# wemos_d1_mini_pro.net
KiCad netlist of a schematic drawn in EAGLE
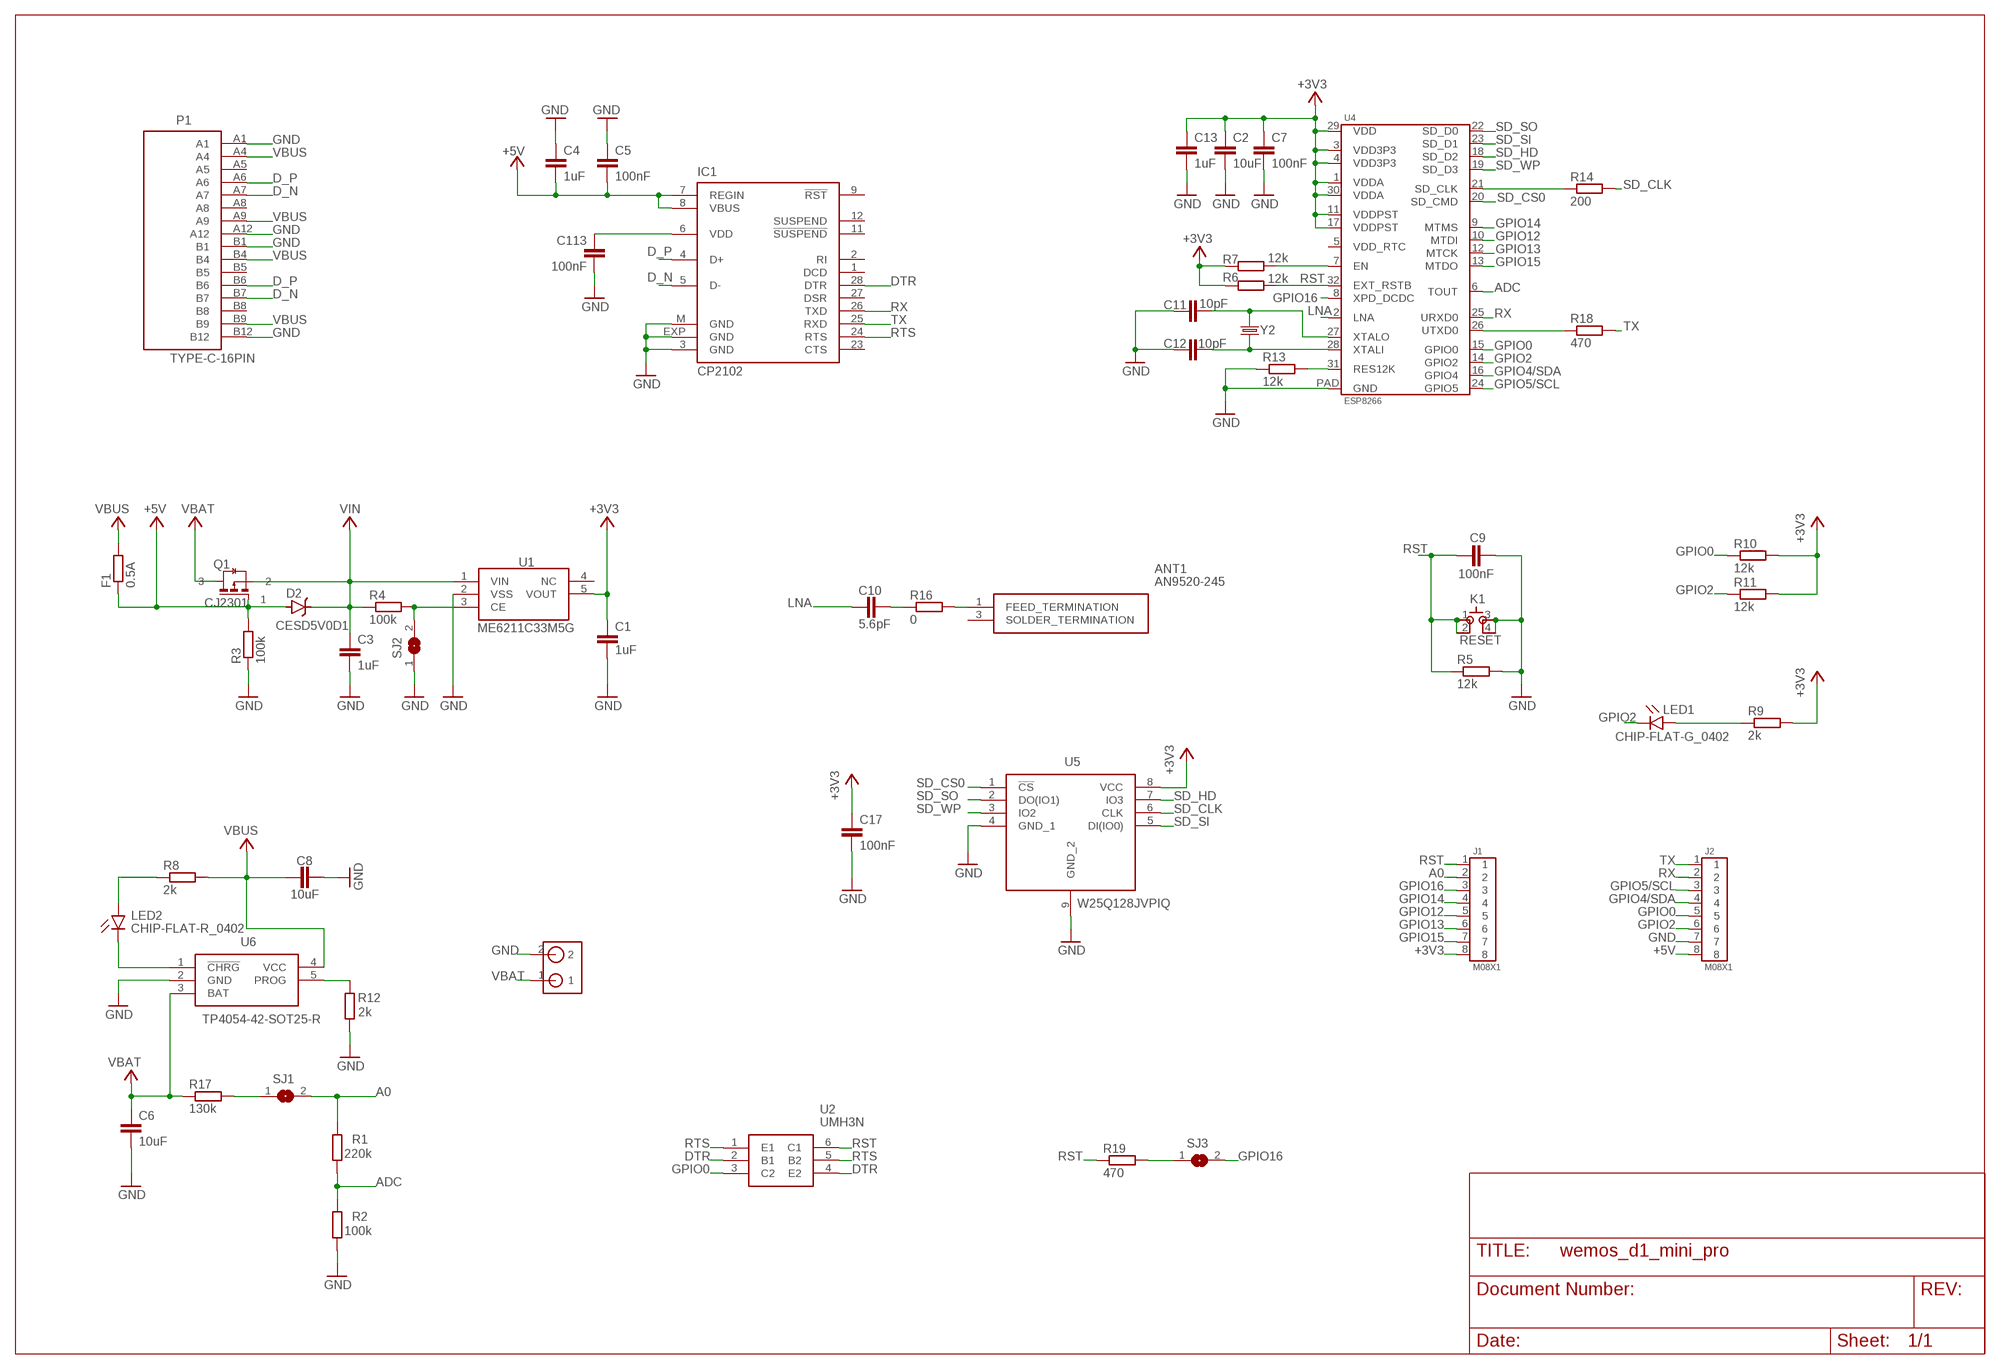
[diagram p0: schematic, sheet 1]

(export (version "E")
  (design (tool "Eeschema 10.0.6"))
  (components
    (comp (ref "ANT1")
      (value "AN9520-245")
      (footprint "eagle-import:AN9520245")
      (libsource (lib "eagle-import") (part "AN9520-245"))
    )
    (comp (ref "C1")
      (value "1uF")
      (footprint "eagle-import:C0402")
      (libsource (lib "eagle-import") (part "C-EUC0402"))
    )
    (comp (ref "C2")
      (value "10uF")
      (footprint "eagle-import:C0402")
      (libsource (lib "eagle-import") (part "C-EUC0402"))
    )
    (comp (ref "C3")
      (value "1uF")
      (footprint "eagle-import:C0402")
      (libsource (lib "eagle-import") (part "C-EUC0402"))
    )
    (comp (ref "C4")
      (value "1uF")
      (footprint "eagle-import:C0402")
      (libsource (lib "eagle-import") (part "C-EUC0402"))
    )
    (comp (ref "C5")
      (value "100nF")
      (footprint "eagle-import:C0402")
      (libsource (lib "eagle-import") (part "C-EUC0402"))
    )
    (comp (ref "C6")
      (value "10uF")
      (footprint "eagle-import:C0402")
      (libsource (lib "eagle-import") (part "C-EUC0402"))
    )
    (comp (ref "C7")
      (value "100nF")
      (footprint "eagle-import:C0402")
      (libsource (lib "eagle-import") (part "C-EUC0402"))
    )
    (comp (ref "C8")
      (value "10uF")
      (footprint "eagle-import:C0402")
      (libsource (lib "eagle-import") (part "C-EUC0402"))
    )
    (comp (ref "C9")
      (value "100nF")
      (footprint "eagle-import:C0402")
      (libsource (lib "eagle-import") (part "C-EUC0402"))
    )
    (comp (ref "C10")
      (value "5.6pF")
      (footprint "eagle-import:C0402")
      (libsource (lib "eagle-import") (part "C-EUC0402"))
    )
    (comp (ref "C11")
      (value "10pF")
      (footprint "eagle-import:C0402")
      (libsource (lib "eagle-import") (part "C-EUC0402"))
    )
    (comp (ref "C12")
      (value "10pF")
      (footprint "eagle-import:C0402")
      (libsource (lib "eagle-import") (part "C-EUC0402"))
    )
    (comp (ref "C13")
      (value "1uF")
      (footprint "eagle-import:C0402")
      (libsource (lib "eagle-import") (part "C-EUC0402"))
    )
    (comp (ref "C17")
      (value "100nF")
      (footprint "eagle-import:C0402")
      (libsource (lib "eagle-import") (part "C-EUC0402"))
    )
    (comp (ref "C113")
      (value "100nF")
      (footprint "eagle-import:C0402")
      (libsource (lib "eagle-import") (part "C-EUC0402"))
    )
    (comp (ref "D2")
      (value "CESD5V0D1")
      (footprint "eagle-import:SOD-123")
      (fields (field (name "MANUFACTURER") "JCET") (field (name "CREATED_BY") "PCBLayout.com"))
      (libsource (lib "eagle-import") (part "CESD5V0D1"))
    )
    (comp (ref "F1")
      (value "0.5A")
      (footprint "eagle-import:R0402")
      (libsource (lib "eagle-import") (part "R-EU_R0402"))
    )
    (comp (ref "IC1")
      (value "CP2102")
      (footprint "eagle-import:MLP28")
      (fields (field (name "MF") "FARNELL") (field (name "MPN") "CP2102-GM"))
      (libsource (lib "eagle-import") (part "CP2102"))
    )
    (comp (ref "J1")
      (value "M08X1")
      (footprint "eagle-import:M08X1")
      (libsource (lib "eagle-import") (part "M08X1"))
    )
    (comp (ref "J2")
      (value "M08X1")
      (footprint "eagle-import:M08X1")
      (libsource (lib "eagle-import") (part "M08X1"))
    )
    (comp (ref "K1")
      (value "RESET")
      (footprint "eagle-import:SKSCLDE010")
      (libsource (lib "eagle-import") (part "SKSCLDE010"))
    )
    (comp (ref "LED1")
      (value "CHIP-FLAT-G_0402")
      (footprint "eagle-import:LEDC1005X25N_FLAT-G")
      (libsource (lib "eagle-import") (part "CHIP-FLAT-G_0402"))
    )
    (comp (ref "LED2")
      (value "CHIP-FLAT-R_0402")
      (footprint "eagle-import:LEDC1005X25N_FLAT-R")
      (libsource (lib "eagle-import") (part "CHIP-FLAT-R_0402"))
    )
    (comp (ref "P1")
      (value "TYPE-C-16PIN")
      (footprint "eagle-import:TYPE-C-16PIN")
      (libsource (lib "eagle-import") (part "TYPE-C-16PIN"))
    )
    (comp (ref "Q1")
      (value "CJ2301")
      (footprint "eagle-import:SOT95P240X115-3N")
      (libsource (lib "eagle-import") (part "CJ2301"))
    )
    (comp (ref "R1")
      (value "220k")
      (footprint "eagle-import:R0402")
      (libsource (lib "eagle-import") (part "R-EU_R0402"))
    )
    (comp (ref "R2")
      (value "100k")
      (footprint "eagle-import:R0402")
      (libsource (lib "eagle-import") (part "R-EU_R0402"))
    )
    (comp (ref "R3")
      (value "100k")
      (footprint "eagle-import:R0402")
      (libsource (lib "eagle-import") (part "R-EU_R0402"))
    )
    (comp (ref "R4")
      (value "100k")
      (footprint "eagle-import:R0402")
      (libsource (lib "eagle-import") (part "R-EU_R0402"))
    )
    (comp (ref "R5")
      (value "12k")
      (footprint "eagle-import:R0402")
      (libsource (lib "eagle-import") (part "R-EU_R0402"))
    )
    (comp (ref "R6")
      (value "12k")
      (footprint "eagle-import:R0402")
      (libsource (lib "eagle-import") (part "R-EU_R0402"))
    )
    (comp (ref "R7")
      (value "12k")
      (footprint "eagle-import:R0402")
      (libsource (lib "eagle-import") (part "R-EU_R0402"))
    )
    (comp (ref "R8")
      (value "2k")
      (footprint "eagle-import:R0402")
      (libsource (lib "eagle-import") (part "R-EU_R0402"))
    )
    (comp (ref "R9")
      (value "2k")
      (footprint "eagle-import:R0402")
      (libsource (lib "eagle-import") (part "R-EU_R0402"))
    )
    (comp (ref "R10")
      (value "12k")
      (footprint "eagle-import:R0402")
      (libsource (lib "eagle-import") (part "R-EU_R0402"))
    )
    (comp (ref "R11")
      (value "12k")
      (footprint "eagle-import:R0402")
      (libsource (lib "eagle-import") (part "R-EU_R0402"))
    )
    (comp (ref "R12")
      (value "2k")
      (footprint "eagle-import:R0402")
      (libsource (lib "eagle-import") (part "R-EU_R0402"))
    )
    (comp (ref "R13")
      (value "12k")
      (footprint "eagle-import:R0402")
      (libsource (lib "eagle-import") (part "R-EU_R0402"))
    )
    (comp (ref "R14")
      (value "200")
      (footprint "eagle-import:R0402")
      (libsource (lib "eagle-import") (part "R-EU_R0402"))
    )
    (comp (ref "R16")
      (value "0")
      (footprint "eagle-import:R0402")
      (libsource (lib "eagle-import") (part "R-EU_R0402"))
    )
    (comp (ref "R17")
      (value "130k")
      (footprint "eagle-import:R0402")
      (libsource (lib "eagle-import") (part "R-EU_R0402"))
    )
    (comp (ref "R18")
      (value "470")
      (footprint "eagle-import:R0402")
      (libsource (lib "eagle-import") (part "R-EU_R0402"))
    )
    (comp (ref "R19")
      (value "470")
      (footprint "eagle-import:R0402")
      (libsource (lib "eagle-import") (part "R-EU_R0402"))
    )
    (comp (ref "SJ1") (value "SJ") (footprint "eagle-import:SJ") (libsource (lib "eagle-import") (part "SJ")))
    (comp (ref "SJ2") (value "SJ") (footprint "eagle-import:SJ") (libsource (lib "eagle-import") (part "SJ")))
    (comp (ref "SJ3") (value "SJ") (footprint "eagle-import:SJ") (libsource (lib "eagle-import") (part "SJ")))
    (comp (ref "U$1")
      (value "ZH1.25")
      (footprint "eagle-import:1.25X2-FLAT")
      (libsource (lib "eagle-import") (part "ZH1.25"))
    )
    (comp (ref "U1")
      (value "ME6211C33M5G")
      (footprint "eagle-import:SOT95P282X145-5N")
      (libsource (lib "eagle-import") (part "ME6211C33M5G"))
    )
    (comp (ref "U2")
      (value "UMH3N")
      (footprint "eagle-import:SOT65P230X110-6N")
      (libsource (lib "eagle-import") (part "UMH3N"))
    )
    (comp (ref "U4")
      (value "ESP8266")
      (footprint "eagle-import:ESP8266")
      (libsource (lib "eagle-import") (part "ESP8266"))
    )
    (comp (ref "U5")
      (value "W25Q128JVPIQ")
      (footprint "eagle-import:SON127P800X600X80-9N")
      (fields (field (name "MOUSER_PART_NUMBER") "454-W25Q128JVPIQ"))
      (libsource (lib "eagle-import") (part "W25Q128JVPIQ"))
    )
    (comp (ref "U6")
      (value "TP4054-42-SOT25-R")
      (footprint "eagle-import:SOT95P280X100-5N")
      (libsource (lib "eagle-import") (part "TP4054-42-SOT25-R"))
    )
    (comp (ref "Y2")
      (value "YSX321SL")
      (footprint "eagle-import:SMD-3225-4")
      (libsource (lib "eagle-import") (part "YSX321SL"))
    )
  )
  (nets
    (net (code "1") (name "+3V3") (class "Default")
      (node (ref "C1") (pin "1") (pinfunction "1_1") (pintype "passive"))
      (node (ref "C13") (pin "1") (pinfunction "1_1") (pintype "passive"))
      (node (ref "C17") (pin "1") (pinfunction "1_1") (pintype "passive"))
      (node (ref "C2") (pin "1") (pinfunction "1_1") (pintype "passive"))
      (node (ref "C7") (pin "1") (pinfunction "1_1") (pintype "passive"))
      (node (ref "J1") (pin "8") (pinfunction "8_8") (pintype "bidirectional"))
      (node (ref "R10") (pin "2") (pinfunction "2_2") (pintype "passive"))
      (node (ref "R11") (pin "2") (pinfunction "2_2") (pintype "passive"))
      (node (ref "R6") (pin "1") (pinfunction "1_1") (pintype "passive"))
      (node (ref "R7") (pin "1") (pinfunction "1_1") (pintype "passive"))
      (node (ref "R9") (pin "2") (pinfunction "2_2") (pintype "passive"))
      (node (ref "U1") (pin "5") (pinfunction "VOUT_5") (pintype "bidirectional"))
      (node (ref "U4") (pin "1") (pinfunction "VDDA_1") (pintype "bidirectional"))
      (node (ref "U4") (pin "11") (pinfunction "VDDPST_11") (pintype "bidirectional"))
      (node (ref "U4") (pin "17") (pinfunction "VDDPST_17") (pintype "bidirectional"))
      (node (ref "U4") (pin "29") (pinfunction "VDD_29") (pintype "bidirectional"))
      (node (ref "U4") (pin "3") (pinfunction "VDD3P3_3") (pintype "bidirectional"))
      (node (ref "U4") (pin "30") (pinfunction "VDDA_30") (pintype "bidirectional"))
      (node (ref "U4") (pin "4") (pinfunction "VDD3P3_4") (pintype "bidirectional"))
      (node (ref "U5") (pin "8") (pinfunction "VCC_8") (pintype "bidirectional"))
    )
    (net (code "2") (name "+5V") (class "Default")
      (node (ref "C4") (pin "2") (pinfunction "2_2") (pintype "passive"))
      (node (ref "C5") (pin "2") (pinfunction "2_2") (pintype "passive"))
      (node (ref "D2") (pin "A") (pinfunction "A_A") (pintype "passive"))
      (node (ref "F1") (pin "1") (pinfunction "1_1") (pintype "passive"))
      (node (ref "IC1") (pin "7") (pinfunction "REGIN_7") (pintype "passive"))
      (node (ref "IC1") (pin "8") (pinfunction "VBUS_8") (pintype "input"))
      (node (ref "J2") (pin "8") (pinfunction "8_8") (pintype "bidirectional"))
      (node (ref "Q1") (pin "1") (pinfunction "1_1") (pintype "bidirectional"))
      (node (ref "R3") (pin "2") (pinfunction "2_2") (pintype "passive"))
    )
    (net (code "3") (name "/A0") (class "Default")
      (node (ref "J1") (pin "2") (pinfunction "2_2") (pintype "bidirectional"))
      (node (ref "R1") (pin "2") (pinfunction "2_2") (pintype "passive"))
      (node (ref "SJ1") (pin "2") (pinfunction "2_2") (pintype "passive"))
    )
    (net (code "4") (name "/ADC") (class "Default")
      (node (ref "R1") (pin "1") (pinfunction "1_1") (pintype "passive"))
      (node (ref "R2") (pin "2") (pinfunction "2_2") (pintype "passive"))
      (node (ref "U4") (pin "6") (pinfunction "TOUT_6") (pintype "bidirectional"))
    )
    (net (code "5") (name "/DTR") (class "Default")
      (node (ref "IC1") (pin "28") (pinfunction "DTR_28") (pintype "output"))
      (node (ref "U2") (pin "2") (pinfunction "B1_2") (pintype "bidirectional"))
      (node (ref "U2") (pin "4") (pinfunction "E2_4") (pintype "bidirectional"))
    )
    (net (code "6") (name "/D_N") (class "Default")
      (node (ref "IC1") (pin "5") (pinfunction "D-_5") (pintype "bidirectional"))
      (node (ref "P1") (pin "A7") (pinfunction "A7_A7") (pintype "bidirectional"))
      (node (ref "P1") (pin "B7") (pinfunction "B7_B7") (pintype "bidirectional"))
    )
    (net (code "7") (name "/D_P") (class "Default")
      (node (ref "IC1") (pin "4") (pinfunction "D+_4") (pintype "bidirectional"))
      (node (ref "P1") (pin "A6") (pinfunction "A6_A6") (pintype "bidirectional"))
      (node (ref "P1") (pin "B6") (pinfunction "B6_B6") (pintype "bidirectional"))
    )
    (net (code "8") (name "/GPIO0") (class "Default")
      (node (ref "J2") (pin "5") (pinfunction "5_5") (pintype "bidirectional"))
      (node (ref "R10") (pin "1") (pinfunction "1_1") (pintype "passive"))
      (node (ref "U2") (pin "3") (pinfunction "C2_3") (pintype "bidirectional"))
      (node (ref "U4") (pin "15") (pinfunction "GPIO0_15") (pintype "bidirectional"))
    )
    (net (code "9") (name "/GPIO2") (class "Default")
      (node (ref "J2") (pin "6") (pinfunction "6_6") (pintype "bidirectional"))
      (node (ref "LED1") (pin "C") (pinfunction "C_C") (pintype "passive"))
      (node (ref "R11") (pin "1") (pinfunction "1_1") (pintype "passive"))
      (node (ref "U4") (pin "14") (pinfunction "GPIO2_14") (pintype "bidirectional"))
    )
    (net (code "10") (name "/GPIO4{slash}SDA") (class "Default")
      (node (ref "J2") (pin "4") (pinfunction "4_4") (pintype "bidirectional"))
      (node (ref "U4") (pin "16") (pinfunction "GPIO4_16") (pintype "bidirectional"))
    )
    (net (code "11") (name "/GPIO5{slash}SCL") (class "Default")
      (node (ref "J2") (pin "3") (pinfunction "3_3") (pintype "bidirectional"))
      (node (ref "U4") (pin "24") (pinfunction "GPIO5_24") (pintype "bidirectional"))
    )
    (net (code "12") (name "/GPIO12") (class "Default")
      (node (ref "J1") (pin "5") (pinfunction "5_5") (pintype "bidirectional"))
      (node (ref "U4") (pin "10") (pinfunction "MTDI_10") (pintype "bidirectional"))
    )
    (net (code "13") (name "/GPIO13") (class "Default")
      (node (ref "J1") (pin "6") (pinfunction "6_6") (pintype "bidirectional"))
      (node (ref "U4") (pin "12") (pinfunction "MTCK_12") (pintype "bidirectional"))
    )
    (net (code "14") (name "/GPIO14") (class "Default")
      (node (ref "J1") (pin "4") (pinfunction "4_4") (pintype "bidirectional"))
      (node (ref "U4") (pin "9") (pinfunction "MTMS_9") (pintype "bidirectional"))
    )
    (net (code "15") (name "/GPIO15") (class "Default")
      (node (ref "J1") (pin "7") (pinfunction "7_7") (pintype "bidirectional"))
      (node (ref "U4") (pin "13") (pinfunction "MTDO_13") (pintype "bidirectional"))
    )
    (net (code "16") (name "/GPIO16") (class "Default")
      (node (ref "J1") (pin "3") (pinfunction "3_3") (pintype "bidirectional"))
      (node (ref "SJ3") (pin "2") (pinfunction "2_2") (pintype "passive"))
      (node (ref "U4") (pin "8") (pinfunction "XPD_DCDC_8") (pintype "bidirectional"))
    )
    (net (code "17") (name "/LNA") (class "Default")
      (node (ref "C10") (pin "1") (pinfunction "1_1") (pintype "passive"))
      (node (ref "U4") (pin "2") (pinfunction "LNA_2") (pintype "bidirectional"))
    )
    (net (code "18") (name "/RST") (class "Default")
      (node (ref "C9") (pin "1") (pinfunction "1_1") (pintype "passive"))
      (node (ref "J1") (pin "1") (pinfunction "1_1") (pintype "bidirectional"))
      (node (ref "K1") (pin "1") (pinfunction "1_1") (pintype "bidirectional"))
      (node (ref "K1") (pin "2") (pinfunction "2_2") (pintype "bidirectional"))
      (node (ref "R19") (pin "1") (pinfunction "1_1") (pintype "passive"))
      (node (ref "R5") (pin "1") (pinfunction "1_1") (pintype "passive"))
      (node (ref "R6") (pin "2") (pinfunction "2_2") (pintype "passive"))
      (node (ref "U2") (pin "6") (pinfunction "C1_6") (pintype "bidirectional"))
      (node (ref "U4") (pin "32") (pinfunction "EXT_RSTB_32") (pintype "bidirectional"))
    )
    (net (code "19") (name "/RTS") (class "Default")
      (node (ref "IC1") (pin "24") (pinfunction "RTS_24") (pintype "output"))
      (node (ref "U2") (pin "1") (pinfunction "E1_1") (pintype "bidirectional"))
      (node (ref "U2") (pin "5") (pinfunction "B2_5") (pintype "bidirectional"))
    )
    (net (code "20") (name "/RX") (class "Default")
      (node (ref "IC1") (pin "26") (pinfunction "TXD_26") (pintype "output"))
      (node (ref "J2") (pin "2") (pinfunction "2_2") (pintype "bidirectional"))
      (node (ref "U4") (pin "25") (pinfunction "URXD0_25") (pintype "bidirectional"))
    )
    (net (code "21") (name "/SD_CLK") (class "Default")
      (node (ref "R14") (pin "2") (pinfunction "2_2") (pintype "passive"))
      (node (ref "U5") (pin "6") (pinfunction "CLK_6") (pintype "bidirectional"))
    )
    (net (code "22") (name "/SD_CS0") (class "Default")
      (node (ref "U4") (pin "20") (pinfunction "SD_CMD_20") (pintype "bidirectional"))
      (node (ref "U5") (pin "1") (pinfunction "~{CS}_1") (pintype "bidirectional"))
    )
    (net (code "23") (name "/SD_HD") (class "Default")
      (node (ref "U4") (pin "18") (pinfunction "SD_D2_18") (pintype "bidirectional"))
      (node (ref "U5") (pin "7") (pinfunction "IO3_7") (pintype "bidirectional"))
    )
    (net (code "24") (name "/SD_SI") (class "Default")
      (node (ref "U4") (pin "23") (pinfunction "SD_D1_23") (pintype "bidirectional"))
      (node (ref "U5") (pin "5") (pinfunction "DI(IO0)_5") (pintype "bidirectional"))
    )
    (net (code "25") (name "/SD_SO") (class "Default")
      (node (ref "U4") (pin "22") (pinfunction "SD_D0_22") (pintype "bidirectional"))
      (node (ref "U5") (pin "2") (pinfunction "DO(IO1)_2") (pintype "bidirectional"))
    )
    (net (code "26") (name "/SD_WP") (class "Default")
      (node (ref "U4") (pin "19") (pinfunction "SD_D3_19") (pintype "bidirectional"))
      (node (ref "U5") (pin "3") (pinfunction "IO2_3") (pintype "bidirectional"))
    )
    (net (code "27") (name "/TX") (class "Default")
      (node (ref "IC1") (pin "25") (pinfunction "RXD_25") (pintype "input"))
      (node (ref "J2") (pin "1") (pinfunction "1_1") (pintype "bidirectional"))
      (node (ref "R18") (pin "2") (pinfunction "2_2") (pintype "passive"))
    )
    (net (code "28") (name "GND") (class "Default")
      (node (ref "C1") (pin "2") (pinfunction "2_2") (pintype "passive"))
      (node (ref "C11") (pin "1") (pinfunction "1_1") (pintype "passive"))
      (node (ref "C113") (pin "2") (pinfunction "2_2") (pintype "passive"))
      (node (ref "C12") (pin "1") (pinfunction "1_1") (pintype "passive"))
      (node (ref "C13") (pin "2") (pinfunction "2_2") (pintype "passive"))
      (node (ref "C17") (pin "2") (pinfunction "2_2") (pintype "passive"))
      (node (ref "C2") (pin "2") (pinfunction "2_2") (pintype "passive"))
      (node (ref "C3") (pin "2") (pinfunction "2_2") (pintype "passive"))
      (node (ref "C4") (pin "1") (pinfunction "1_1") (pintype "passive"))
      (node (ref "C5") (pin "1") (pinfunction "1_1") (pintype "passive"))
      (node (ref "C6") (pin "2") (pinfunction "2_2") (pintype "passive"))
      (node (ref "C7") (pin "2") (pinfunction "2_2") (pintype "passive"))
      (node (ref "C8") (pin "2") (pinfunction "2_2") (pintype "passive"))
      (node (ref "C9") (pin "2") (pinfunction "2_2") (pintype "passive"))
      (node (ref "IC1") (pin "3") (pinfunction "GND_3") (pintype "power_in"))
      (node (ref "IC1") (pin "EXP") (pinfunction "GND_EXP") (pintype "power_in"))
      (node (ref "IC1") (pin "M") (pinfunction "GND_M") (pintype "power_in"))
      (node (ref "J2") (pin "7") (pinfunction "7_7") (pintype "bidirectional"))
      (node (ref "K1") (pin "3") (pinfunction "4_3") (pintype "bidirectional"))
      (node (ref "K1") (pin "4") (pinfunction "3_4") (pintype "bidirectional"))
      (node (ref "P1") (pin "A1") (pinfunction "A1_A1") (pintype "bidirectional"))
      (node (ref "P1") (pin "A12") (pinfunction "A12_A12") (pintype "bidirectional"))
      (node (ref "P1") (pin "B1") (pinfunction "B1_B1") (pintype "bidirectional"))
      (node (ref "P1") (pin "B12") (pinfunction "B12_B12") (pintype "bidirectional"))
      (node (ref "R12") (pin "1") (pinfunction "1_1") (pintype "passive"))
      (node (ref "R13") (pin "1") (pinfunction "1_1") (pintype "passive"))
      (node (ref "R2") (pin "1") (pinfunction "1_1") (pintype "passive"))
      (node (ref "R3") (pin "1") (pinfunction "1_1") (pintype "passive"))
      (node (ref "R5") (pin "2") (pinfunction "2_2") (pintype "passive"))
      (node (ref "SJ2") (pin "1") (pinfunction "1_1") (pintype "passive"))
      (node (ref "U$1") (pin "2") (pinfunction "2_2") (pintype "bidirectional"))
      (node (ref "U1") (pin "2") (pinfunction "VSS_2") (pintype "bidirectional"))
      (node (ref "U4") (pin "PAD") (pinfunction "GND_PAD") (pintype "bidirectional"))
      (node (ref "U5") (pin "4") (pinfunction "GND_1_4") (pintype "bidirectional"))
      (node (ref "U5") (pin "9") (pinfunction "GND_2_9") (pintype "bidirectional"))
      (node (ref "U6") (pin "2") (pinfunction "GND_2") (pintype "bidirectional"))
    )
    (net (code "29") (name "Net-(ANT1-FEED_TERMINATION)") (class "Default")
      (node (ref "ANT1") (pin "1") (pinfunction "FEED_TERMINATION_1") (pintype "bidirectional"))
      (node (ref "R16") (pin "2") (pinfunction "2_2") (pintype "passive"))
    )
    (net (code "30") (name "Net-(C10-Pad2)") (class "Default")
      (node (ref "C10") (pin "2") (pinfunction "2_2") (pintype "passive"))
      (node (ref "R16") (pin "1") (pinfunction "1_1") (pintype "passive"))
    )
    (net (code "31") (name "Net-(IC1-VDD)") (class "Default")
      (node (ref "C113") (pin "1") (pinfunction "1_1") (pintype "passive"))
      (node (ref "IC1") (pin "6") (pinfunction "VDD_6") (pintype "power_in"))
    )
    (net (code "32") (name "Net-(LED1-PadA)") (class "Default")
      (node (ref "LED1") (pin "A") (pinfunction "A_A") (pintype "passive"))
      (node (ref "R9") (pin "1") (pinfunction "1_1") (pintype "passive"))
    )
    (net (code "33") (name "Net-(LED2-PadA)") (class "Default")
      (node (ref "LED2") (pin "A") (pinfunction "A_A") (pintype "passive"))
      (node (ref "R8") (pin "1") (pinfunction "1_1") (pintype "passive"))
    )
    (net (code "34") (name "Net-(R17-Pad2)") (class "Default")
      (node (ref "R17") (pin "2") (pinfunction "2_2") (pintype "passive"))
      (node (ref "SJ1") (pin "1") (pinfunction "1_1") (pintype "passive"))
    )
    (net (code "35") (name "Net-(R19-Pad2)") (class "Default")
      (node (ref "R19") (pin "2") (pinfunction "2_2") (pintype "passive"))
      (node (ref "SJ3") (pin "1") (pinfunction "1_1") (pintype "passive"))
    )
    (net (code "36") (name "Net-(U1-CE)") (class "Default")
      (node (ref "R4") (pin "2") (pinfunction "2_2") (pintype "passive"))
      (node (ref "SJ2") (pin "2") (pinfunction "2_2") (pintype "passive"))
      (node (ref "U1") (pin "3") (pinfunction "CE_3") (pintype "bidirectional"))
    )
    (net (code "37") (name "Net-(U4-EN)") (class "Default")
      (node (ref "R7") (pin "2") (pinfunction "2_2") (pintype "passive"))
      (node (ref "U4") (pin "7") (pinfunction "EN_7") (pintype "bidirectional"))
    )
    (net (code "38") (name "Net-(U4-RES12K)") (class "Default")
      (node (ref "R13") (pin "2") (pinfunction "2_2") (pintype "passive"))
      (node (ref "U4") (pin "31") (pinfunction "RES12K_31") (pintype "bidirectional"))
    )
    (net (code "39") (name "Net-(U4-SD_CLK)") (class "Default")
      (node (ref "R14") (pin "1") (pinfunction "1_1") (pintype "passive"))
      (node (ref "U4") (pin "21") (pinfunction "SD_CLK_21") (pintype "bidirectional"))
    )
    (net (code "40") (name "Net-(U4-UTXD0)") (class "Default")
      (node (ref "R18") (pin "1") (pinfunction "1_1") (pintype "passive"))
      (node (ref "U4") (pin "26") (pinfunction "UTXD0_26") (pintype "bidirectional"))
    )
    (net (code "41") (name "Net-(U4-XTALI)") (class "Default")
      (node (ref "C12") (pin "2") (pinfunction "2_2") (pintype "passive"))
      (node (ref "U4") (pin "28") (pinfunction "XTALI_28") (pintype "bidirectional"))
      (node (ref "Y2") (pin "1") (pinfunction "P$1_1") (pintype "bidirectional"))
    )
    (net (code "42") (name "Net-(U4-XTALO)") (class "Default")
      (node (ref "C11") (pin "2") (pinfunction "2_2") (pintype "passive"))
      (node (ref "U4") (pin "27") (pinfunction "XTALO_27") (pintype "bidirectional"))
      (node (ref "Y2") (pin "3") (pinfunction "P$2_3") (pintype "bidirectional"))
    )
    (net (code "43") (name "Net-(U6-PROG)") (class "Default")
      (node (ref "R12") (pin "2") (pinfunction "2_2") (pintype "passive"))
      (node (ref "U6") (pin "5") (pinfunction "PROG_5") (pintype "bidirectional"))
    )
    (net (code "44") (name "Net-(U6-~{CHRG})") (class "Default")
      (node (ref "LED2") (pin "C") (pinfunction "C_C") (pintype "passive"))
      (node (ref "U6") (pin "1") (pinfunction "~{CHRG}_1") (pintype "bidirectional"))
    )
    (net (code "45") (name "VBAT") (class "Default")
      (node (ref "C6") (pin "1") (pinfunction "1_1") (pintype "passive"))
      (node (ref "Q1") (pin "3") (pinfunction "3_3") (pintype "bidirectional"))
      (node (ref "R17") (pin "1") (pinfunction "1_1") (pintype "passive"))
      (node (ref "U$1") (pin "1") (pinfunction "1_1") (pintype "bidirectional"))
      (node (ref "U6") (pin "3") (pinfunction "BAT_3") (pintype "bidirectional"))
    )
    (net (code "46") (name "VBUS") (class "Default")
      (node (ref "C8") (pin "1") (pinfunction "1_1") (pintype "passive"))
      (node (ref "F1") (pin "2") (pinfunction "2_2") (pintype "passive"))
      (node (ref "P1") (pin "A4") (pinfunction "A4_A4") (pintype "bidirectional"))
      (node (ref "P1") (pin "A9") (pinfunction "A9_A9") (pintype "bidirectional"))
      (node (ref "P1") (pin "B4") (pinfunction "B4_B4") (pintype "bidirectional"))
      (node (ref "P1") (pin "B9") (pinfunction "B9_B9") (pintype "bidirectional"))
      (node (ref "R8") (pin "2") (pinfunction "2_2") (pintype "passive"))
      (node (ref "U6") (pin "4") (pinfunction "VCC_4") (pintype "bidirectional"))
    )
    (net (code "47") (name "VIN") (class "Default")
      (node (ref "C3") (pin "1") (pinfunction "1_1") (pintype "passive"))
      (node (ref "D2") (pin "C") (pinfunction "C_C") (pintype "passive"))
      (node (ref "Q1") (pin "2") (pinfunction "2_2") (pintype "bidirectional"))
      (node (ref "R4") (pin "1") (pinfunction "1_1") (pintype "passive"))
      (node (ref "U1") (pin "1") (pinfunction "VIN_1") (pintype "bidirectional"))
    )
    (net (code "48") (name "unconnected-(ANT1-SOLDER_TERMINATION-Pad3)") (class "Default")
      (node (ref "ANT1") (pin "3") (pinfunction "SOLDER_TERMINATION_3") (pintype "bidirectional"))
    )
    (net (code "49") (name "unconnected-(IC1-CTS-Pad23)") (class "Default")
      (node (ref "IC1") (pin "23") (pinfunction "CTS_23") (pintype "input"))
    )
    (net (code "50") (name "unconnected-(IC1-DCD-Pad1)") (class "Default")
      (node (ref "IC1") (pin "1") (pinfunction "DCD_1") (pintype "input"))
    )
    (net (code "51") (name "unconnected-(IC1-DSR-Pad27)") (class "Default")
      (node (ref "IC1") (pin "27") (pinfunction "DSR_27") (pintype "input"))
    )
    (net (code "52") (name "unconnected-(IC1-RI-Pad2)") (class "Default")
      (node (ref "IC1") (pin "2") (pinfunction "RI_2") (pintype "input"))
    )
    (net (code "53") (name "unconnected-(IC1-SUSPEND-Pad12)") (class "Default")
      (node (ref "IC1") (pin "12") (pinfunction "SUSPEND_12") (pintype "output"))
    )
    (net (code "54") (name "unconnected-(IC1-~{RST}-Pad9)") (class "Default")
      (node (ref "IC1") (pin "9") (pinfunction "~{RST}_9") (pintype "bidirectional"))
    )
    (net (code "55") (name "unconnected-(IC1-~{SUSPEND}-Pad11)") (class "Default")
      (node (ref "IC1") (pin "11") (pinfunction "~{SUSPEND}_11") (pintype "output"))
    )
    (net (code "56") (name "unconnected-(P1-PadA5)") (class "Default")
      (node (ref "P1") (pin "A5") (pinfunction "A5_A5") (pintype "bidirectional"))
    )
    (net (code "57") (name "unconnected-(P1-PadA8)") (class "Default")
      (node (ref "P1") (pin "A8") (pinfunction "A8_A8") (pintype "bidirectional"))
    )
    (net (code "58") (name "unconnected-(P1-PadB5)") (class "Default")
      (node (ref "P1") (pin "B5") (pinfunction "B5_B5") (pintype "bidirectional"))
    )
    (net (code "59") (name "unconnected-(P1-PadB8)") (class "Default")
      (node (ref "P1") (pin "B8") (pinfunction "B8_B8") (pintype "bidirectional"))
    )
    (net (code "60") (name "unconnected-(U1-NC-Pad4)") (class "Default")
      (node (ref "U1") (pin "4") (pinfunction "NC_4") (pintype "no_connect"))
    )
    (net (code "61") (name "unconnected-(U4-VDD_RTC-Pad5)") (class "Default")
      (node (ref "U4") (pin "5") (pinfunction "VDD_RTC_5") (pintype "bidirectional"))
    )
  )
)
